# 1W_FM_TRX_DRA818V.net
KiCad netlist of a schematic drawn in EAGLE
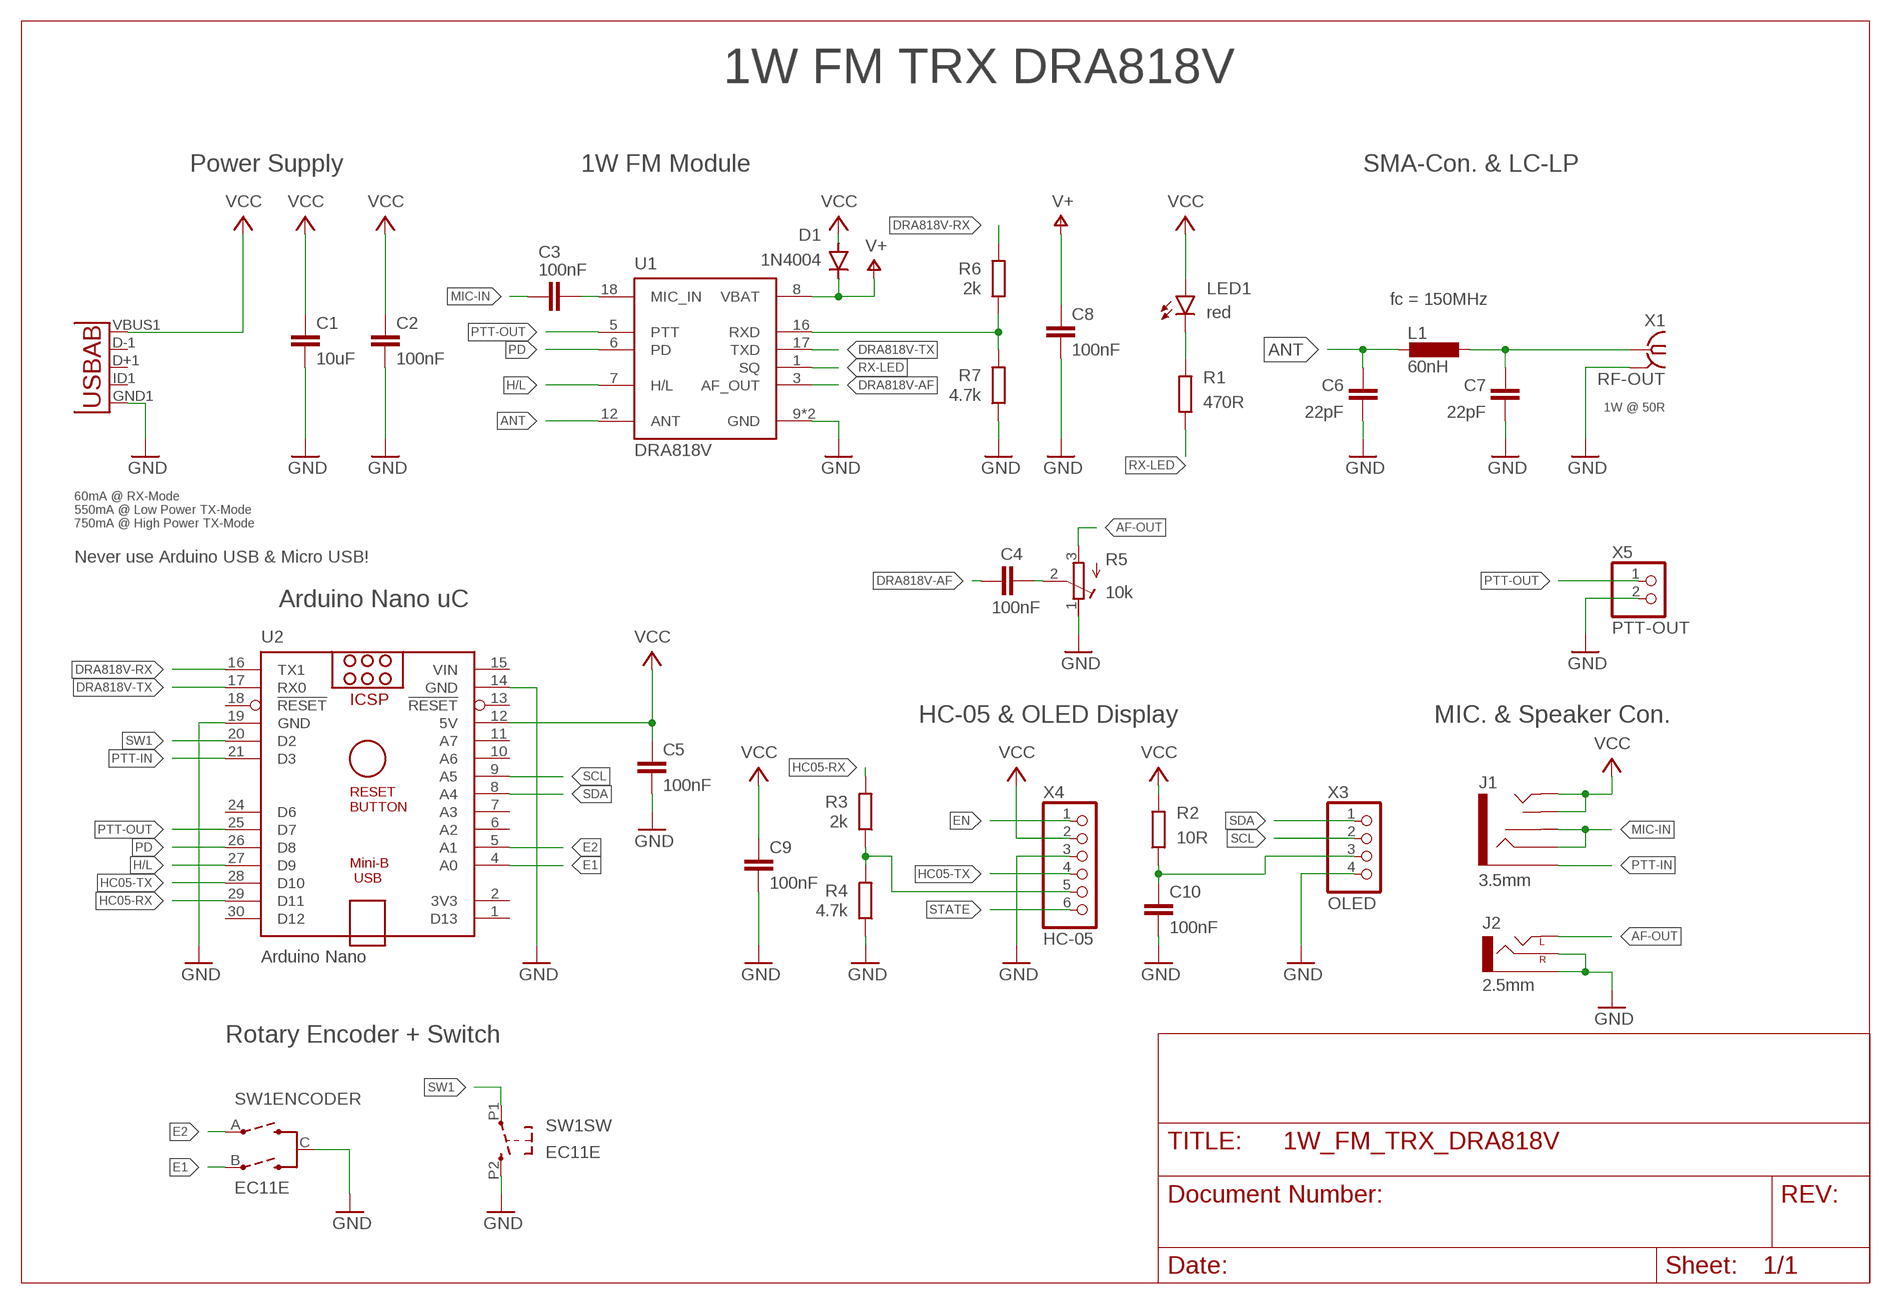
[diagram p0: schematic, sheet 1]

(export (version "E")
  (design (tool "Eeschema 10.0.6"))
  (components
    (comp (ref "C1")
      (value "10uF")
      (footprint "eagle-import:C0805K")
      (libsource (lib "eagle-import") (part "C-EUC0805K"))
    )
    (comp (ref "C2")
      (value "100nF")
      (footprint "eagle-import:C0805K")
      (libsource (lib "eagle-import") (part "C-EUC0805K"))
    )
    (comp (ref "C3")
      (value "100nF")
      (footprint "eagle-import:C0805K")
      (libsource (lib "eagle-import") (part "C-EUC0805K"))
    )
    (comp (ref "C4")
      (value "100nF")
      (footprint "eagle-import:C0805K")
      (libsource (lib "eagle-import") (part "C-EUC0805K"))
    )
    (comp (ref "C5")
      (value "100nF")
      (footprint "eagle-import:C0805K")
      (libsource (lib "eagle-import") (part "C-EUC0805K"))
    )
    (comp (ref "C6")
      (value "22pF")
      (footprint "eagle-import:C0805K")
      (libsource (lib "eagle-import") (part "C-EUC0805K"))
    )
    (comp (ref "C7")
      (value "22pF")
      (footprint "eagle-import:C0805K")
      (libsource (lib "eagle-import") (part "C-EUC0805K"))
    )
    (comp (ref "C8")
      (value "100nF")
      (footprint "eagle-import:C0805K")
      (libsource (lib "eagle-import") (part "C-EUC0805K"))
    )
    (comp (ref "C9")
      (value "100nF")
      (footprint "eagle-import:C0805K")
      (libsource (lib "eagle-import") (part "C-EUC0805K"))
    )
    (comp (ref "C10")
      (value "100nF")
      (footprint "eagle-import:C0805K")
      (libsource (lib "eagle-import") (part "C-EUC0805K"))
    )
    (comp (ref "D1")
      (value "1N4004")
      (footprint "eagle-import:DO41-10")
      (libsource (lib "eagle-import") (part "1N4004"))
    )
    (comp (ref "J1")
      (value "3.5mm")
      (footprint "eagle-import:AUDIO-JACK")
      (libsource (lib "eagle-import") (part "AUDIO_JACK_3.5MM_PTH"))
    )
    (comp (ref "J2")
      (value "2.5mm")
      (footprint "eagle-import:STEREOJACK2.5MM_STEREOJACK2.5MM")
      (libsource (lib "eagle-import") (part "AUDIO_JACK_2.5MM_2.5MM"))
    )
    (comp (ref "L1")
      (value "60nH")
      (footprint "eagle-import:L8530M")
      (libsource (lib "eagle-import") (part "L-EUL8530M"))
    )
    (comp (ref "LED1")
      (value "red")
      (footprint "eagle-import:CHIP-LED0805")
      (libsource (lib "eagle-import") (part "LEDCHIP-LED0805"))
    )
    (comp (ref "R1")
      (value "470R")
      (footprint "eagle-import:R0805")
      (libsource (lib "eagle-import") (part "R-EU_R0805"))
    )
    (comp (ref "R2")
      (value "10R")
      (footprint "eagle-import:R0805")
      (libsource (lib "eagle-import") (part "R-EU_R0805"))
    )
    (comp (ref "R3")
      (value "2k")
      (footprint "eagle-import:R0805")
      (libsource (lib "eagle-import") (part "R-EU_R0805"))
    )
    (comp (ref "R4")
      (value "4.7k")
      (footprint "eagle-import:R0805")
      (libsource (lib "eagle-import") (part "R-EU_R0805"))
    )
    (comp (ref "R5")
      (value "10k")
      (footprint "eagle-import:RTRIM3314J")
      (libsource (lib "eagle-import") (part "R-TRIMM3314J"))
    )
    (comp (ref "R6")
      (value "2k")
      (footprint "eagle-import:R0805")
      (libsource (lib "eagle-import") (part "R-EU_R0805"))
    )
    (comp (ref "R7")
      (value "4.7k")
      (footprint "eagle-import:R0805")
      (libsource (lib "eagle-import") (part "R-EU_R0805"))
    )
    (comp (ref "SW1")
      (value "EC11E")
      (footprint "eagle-import:EC11E_INCREMENTAL_ENCODER")
      (libsource (lib "eagle-import") (part "ENCODER_SW1-PEC12"))
    )
    (comp (ref "U1")
      (value "DRA818V")
      (footprint "eagle-import:DORJI_DRA818V")
      (fields (field (name "MF") "DORJI"))
      (libsource (lib "eagle-import") (part "DRA818V"))
    )
    (comp (ref "U2")
      (value "Arduino Nano")
      (footprint "eagle-import:ARDUINO_NANO")
      (libsource (lib "eagle-import") (part "ARDUINO_NANO"))
    )
    (comp (ref "U3")
      (value "USB Micro")
      (footprint "eagle-import:USB-MICRO-SMD")
      (libsource (lib "eagle-import") (part "USB{dblquote}{dblquote}"))
    )
    (comp (ref "X1")
      (value "RF-OUT")
      (footprint "eagle-import:J502-ND-142-0711-821_826")
      (fields (field (name "MF") "JOHNSON COMPONENTS") (field (name "MPN") "142-0711-821"))
      (libsource (lib "eagle-import") (part "SMA-PCB-CON142-0711-821/826"))
    )
    (comp (ref "X3")
      (value "OLED")
      (footprint "eagle-import:1X04")
      (libsource (lib "eagle-import") (part "PINHD-1X4"))
    )
    (comp (ref "X4")
      (value "HC-05")
      (footprint "eagle-import:1X06")
      (libsource (lib "eagle-import") (part "PINHD-1X6"))
    )
    (comp (ref "X5")
      (value "PTT-OUT")
      (footprint "eagle-import:1X02")
      (libsource (lib "eagle-import") (part "PINHD-1X2"))
    )
  )
  (nets
    (net (code "1") (name "/VIN") (class "Default")
      (node (ref "U2") (pin "15") (pinfunction "VIN_15") (pintype "power_in"))
    )
    (net (code "2") (name "AF-OUT") (class "Default")
      (node (ref "J2") (pin "SHIELD") (pinfunction "LEFT_SHIELD") (pintype "bidirectional"))
      (node (ref "R5") (pin "3") (pinfunction "A_3") (pintype "passive"))
    )
    (net (code "3") (name "ANT") (class "Default")
      (node (ref "C6") (pin "2") (pinfunction "2_2") (pintype "passive"))
      (node (ref "L1") (pin "2") (pinfunction "2_2") (pintype "passive"))
      (node (ref "U1") (pin "12") (pinfunction "ANT_12") (pintype "passive"))
    )
    (net (code "4") (name "DRA818V-AF") (class "Default")
      (node (ref "C4") (pin "1") (pinfunction "1_1") (pintype "passive"))
      (node (ref "U1") (pin "3") (pinfunction "AF_OUT_3") (pintype "output"))
    )
    (net (code "5") (name "DRA818V-RX") (class "Default")
      (node (ref "R6") (pin "2") (pinfunction "2_2") (pintype "passive"))
      (node (ref "U2") (pin "16") (pinfunction "TX1_16") (pintype "bidirectional"))
    )
    (net (code "6") (name "DRA818V-TX") (class "Default")
      (node (ref "U1") (pin "17") (pinfunction "TXD_17") (pintype "output"))
      (node (ref "U2") (pin "17") (pinfunction "RX0_17") (pintype "bidirectional"))
    )
    (net (code "7") (name "E1") (class "Default")
      (node (ref "SW1") (pin "B") (pinfunction "B_B") (pintype "passive"))
      (node (ref "U2") (pin "4") (pinfunction "A0_4") (pintype "bidirectional"))
    )
    (net (code "8") (name "E2") (class "Default")
      (node (ref "SW1") (pin "A") (pinfunction "A_A") (pintype "passive"))
      (node (ref "U2") (pin "5") (pinfunction "A1_5") (pintype "bidirectional"))
    )
    (net (code "9") (name "EN") (class "Default")
      (node (ref "X4") (pin "1") (pinfunction "1_1") (pintype "passive"))
    )
    (net (code "10") (name "GND") (class "Default")
      (node (ref "C1") (pin "2") (pinfunction "2_2") (pintype "passive"))
      (node (ref "C10") (pin "2") (pinfunction "2_2") (pintype "passive"))
      (node (ref "C2") (pin "2") (pinfunction "2_2") (pintype "passive"))
      (node (ref "C5") (pin "2") (pinfunction "2_2") (pintype "passive"))
      (node (ref "C6") (pin "1") (pinfunction "1_1") (pintype "passive"))
      (node (ref "C7") (pin "1") (pinfunction "1_1") (pintype "passive"))
      (node (ref "C8") (pin "1") (pinfunction "1_1") (pintype "passive"))
      (node (ref "C9") (pin "2") (pinfunction "2_2") (pintype "passive"))
      (node (ref "J2") (pin "RING1") (pinfunction "SLEEVE_RING1") (pintype "bidirectional"))
      (node (ref "J2") (pin "TIP") (pinfunction "RIGHT_TIP") (pintype "bidirectional"))
      (node (ref "R4") (pin "1") (pinfunction "1_1") (pintype "passive"))
      (node (ref "R5") (pin "1") (pinfunction "E_1") (pintype "passive"))
      (node (ref "R7") (pin "1") (pinfunction "1_1") (pintype "passive"))
      (node (ref "SW1") (pin "C") (pinfunction "C_C") (pintype "passive"))
      (node (ref "SW1") (pin "P2") (pinfunction "2_P2") (pintype "passive"))
      (node (ref "U1") (pin "10") (pinfunction "GND_10") (pintype "power_in"))
      (node (ref "U1") (pin "9") (pinfunction "GND_9") (pintype "power_in"))
      (node (ref "U2") (pin "14") (pinfunction "GND_14") (pintype "power_in"))
      (node (ref "U2") (pin "19") (pinfunction "GND_19") (pintype "power_in"))
      (node (ref "U3") (pin "GND1") (pinfunction "GND_GND1") (pintype "bidirectional"))
      (node (ref "X1") (pin "G@1") (pinfunction "GND_G@1") (pintype "passive"))
      (node (ref "X1") (pin "G@2") (pinfunction "GND_G@2") (pintype "passive"))
      (node (ref "X1") (pin "G@3") (pinfunction "GND_G@3") (pintype "passive"))
      (node (ref "X1") (pin "G@4") (pinfunction "GND_G@4") (pintype "passive"))
      (node (ref "X3") (pin "4") (pinfunction "4_4") (pintype "passive"))
      (node (ref "X4") (pin "3") (pinfunction "3_3") (pintype "passive"))
      (node (ref "X5") (pin "2") (pinfunction "2_2") (pintype "passive"))
    )
    (net (code "11") (name "HC05-RX") (class "Default")
      (node (ref "R3") (pin "2") (pinfunction "2_2") (pintype "passive"))
      (node (ref "U2") (pin "29") (pinfunction "D11_29") (pintype "bidirectional"))
    )
    (net (code "12") (name "HC05-TX") (class "Default")
      (node (ref "U2") (pin "28") (pinfunction "D10_28") (pintype "bidirectional"))
      (node (ref "X4") (pin "4") (pinfunction "4_4") (pintype "passive"))
    )
    (net (code "13") (name "H{slash}L") (class "Default")
      (node (ref "U1") (pin "7") (pinfunction "H/L_7") (pintype "input"))
      (node (ref "U2") (pin "27") (pinfunction "D9_27") (pintype "bidirectional"))
    )
    (net (code "14") (name "MIC-IN") (class "Default")
      (node (ref "C3") (pin "1") (pinfunction "1_1") (pintype "passive"))
      (node (ref "J1") (pin "RING") (pinfunction "RING_RING") (pintype "bidirectional"))
      (node (ref "J1") (pin "RSH") (pinfunction "RSH_RSH") (pintype "bidirectional"))
    )
    (net (code "15") (name "Net-(C10-Pad1)") (class "Default")
      (node (ref "C10") (pin "1") (pinfunction "1_1") (pintype "passive"))
      (node (ref "R2") (pin "1") (pinfunction "1_1") (pintype "passive"))
      (node (ref "X3") (pin "3") (pinfunction "3_3") (pintype "passive"))
    )
    (net (code "16") (name "Net-(LED1-PadC)") (class "Default")
      (node (ref "LED1") (pin "C") (pinfunction "C_C") (pintype "passive"))
      (node (ref "R1") (pin "2") (pinfunction "2_2") (pintype "passive"))
    )
    (net (code "17") (name "Net-(R3-Pad1)") (class "Default")
      (node (ref "R3") (pin "1") (pinfunction "1_1") (pintype "passive"))
      (node (ref "R4") (pin "2") (pinfunction "2_2") (pintype "passive"))
      (node (ref "X4") (pin "5") (pinfunction "5_5") (pintype "passive"))
    )
    (net (code "18") (name "Net-(R5-S)") (class "Default")
      (node (ref "C4") (pin "2") (pinfunction "2_2") (pintype "passive"))
      (node (ref "R5") (pin "2") (pinfunction "S_2") (pintype "passive"))
    )
    (net (code "19") (name "Net-(U1-MIC_IN)") (class "Default")
      (node (ref "C3") (pin "2") (pinfunction "2_2") (pintype "passive"))
      (node (ref "U1") (pin "18") (pinfunction "MIC_IN_18") (pintype "input"))
    )
    (net (code "20") (name "Net-(U1-RXD)") (class "Default")
      (node (ref "R6") (pin "1") (pinfunction "1_1") (pintype "passive"))
      (node (ref "R7") (pin "2") (pinfunction "2_2") (pintype "passive"))
      (node (ref "U1") (pin "16") (pinfunction "RXD_16") (pintype "input"))
    )
    (net (code "21") (name "Net-(X1-RF)") (class "Default")
      (node (ref "C7") (pin "2") (pinfunction "2_2") (pintype "passive"))
      (node (ref "L1") (pin "1") (pinfunction "1_1") (pintype "passive"))
      (node (ref "X1") (pin "1") (pinfunction "RF_1") (pintype "passive"))
    )
    (net (code "22") (name "PD") (class "Default")
      (node (ref "U1") (pin "6") (pinfunction "PD_6") (pintype "input"))
      (node (ref "U2") (pin "26") (pinfunction "D8_26") (pintype "bidirectional"))
    )
    (net (code "23") (name "PTT-IN") (class "Default")
      (node (ref "J1") (pin "SLEEVE") (pinfunction "SLEEVE_SLEEVE") (pintype "bidirectional"))
      (node (ref "U2") (pin "21") (pinfunction "D3_21") (pintype "bidirectional"))
    )
    (net (code "24") (name "PTT-OUT") (class "Default")
      (node (ref "U1") (pin "5") (pinfunction "PTT_5") (pintype "input"))
      (node (ref "U2") (pin "25") (pinfunction "D7_25") (pintype "bidirectional"))
      (node (ref "X5") (pin "1") (pinfunction "1_1") (pintype "passive"))
    )
    (net (code "25") (name "RX-LED") (class "Default")
      (node (ref "R1") (pin "1") (pinfunction "1_1") (pintype "passive"))
      (node (ref "U1") (pin "1") (pinfunction "SQ_1") (pintype "output"))
    )
    (net (code "26") (name "SCL") (class "Default")
      (node (ref "U2") (pin "9") (pinfunction "A5_9") (pintype "bidirectional"))
      (node (ref "X3") (pin "2") (pinfunction "2_2") (pintype "passive"))
    )
    (net (code "27") (name "SDA") (class "Default")
      (node (ref "U2") (pin "8") (pinfunction "A4_8") (pintype "bidirectional"))
      (node (ref "X3") (pin "1") (pinfunction "1_1") (pintype "passive"))
    )
    (net (code "28") (name "STATE") (class "Default")
      (node (ref "X4") (pin "6") (pinfunction "6_6") (pintype "passive"))
    )
    (net (code "29") (name "SW1") (class "Default")
      (node (ref "SW1") (pin "P1") (pinfunction "1_P1") (pintype "passive"))
      (node (ref "U2") (pin "20") (pinfunction "D2_20") (pintype "bidirectional"))
    )
    (net (code "30") (name "V+") (class "Default")
      (node (ref "C8") (pin "2") (pinfunction "2_2") (pintype "passive"))
      (node (ref "D1") (pin "C") (pinfunction "C_C") (pintype "passive"))
      (node (ref "U1") (pin "8") (pinfunction "VBAT_8") (pintype "power_in"))
    )
    (net (code "31") (name "VCC") (class "Default")
      (node (ref "C1") (pin "1") (pinfunction "1_1") (pintype "passive"))
      (node (ref "C2") (pin "1") (pinfunction "1_1") (pintype "passive"))
      (node (ref "C5") (pin "1") (pinfunction "1_1") (pintype "passive"))
      (node (ref "C9") (pin "1") (pinfunction "1_1") (pintype "passive"))
      (node (ref "D1") (pin "A") (pinfunction "A_A") (pintype "passive"))
      (node (ref "J1") (pin "TIP") (pinfunction "TIP_TIP") (pintype "bidirectional"))
      (node (ref "J1") (pin "TSH") (pinfunction "TSH_TSH") (pintype "bidirectional"))
      (node (ref "LED1") (pin "A") (pinfunction "A_A") (pintype "passive"))
      (node (ref "R2") (pin "2") (pinfunction "2_2") (pintype "passive"))
      (node (ref "U2") (pin "12") (pinfunction "5V_12") (pintype "power_in"))
      (node (ref "U3") (pin "VBUS1") (pinfunction "VBUS_VBUS1") (pintype "bidirectional"))
      (node (ref "X4") (pin "2") (pinfunction "2_2") (pintype "passive"))
    )
    (net (code "32") (name "unconnected-(U2-3V3-Pad2)") (class "Default")
      (node (ref "U2") (pin "2") (pinfunction "3V3_2") (pintype "output"))
    )
    (net (code "33") (name "unconnected-(U2-A2-Pad6)") (class "Default")
      (node (ref "U2") (pin "6") (pinfunction "A2_6") (pintype "bidirectional"))
    )
    (net (code "34") (name "unconnected-(U2-A3-Pad7)") (class "Default")
      (node (ref "U2") (pin "7") (pinfunction "A3_7") (pintype "bidirectional"))
    )
    (net (code "35") (name "unconnected-(U2-A6-Pad10)") (class "Default")
      (node (ref "U2") (pin "10") (pinfunction "A6_10") (pintype "bidirectional"))
    )
    (net (code "36") (name "unconnected-(U2-A7-Pad11)") (class "Default")
      (node (ref "U2") (pin "11") (pinfunction "A7_11") (pintype "bidirectional"))
    )
    (net (code "37") (name "unconnected-(U2-D6-Pad24)") (class "Default")
      (node (ref "U2") (pin "24") (pinfunction "D6_24") (pintype "bidirectional"))
    )
    (net (code "38") (name "unconnected-(U2-D12-Pad30)") (class "Default")
      (node (ref "U2") (pin "30") (pinfunction "D12_30") (pintype "bidirectional"))
    )
    (net (code "39") (name "unconnected-(U2-D13-Pad1)") (class "Default")
      (node (ref "U2") (pin "1") (pinfunction "D13_1") (pintype "bidirectional"))
    )
    (net (code "40") (name "unconnected-(U2-~{RESET}-Pad13)") (class "Default")
      (node (ref "U2") (pin "13") (pinfunction "~{RESET}_13") (pintype "input"))
    )
    (net (code "41") (name "unconnected-(U2-~{RESET}-Pad18)") (class "Default")
      (node (ref "U2") (pin "18") (pinfunction "~{RESET}_18") (pintype "input"))
    )
    (net (code "42") (name "unconnected-(U3-D+-PadD+1)") (class "Default")
      (node (ref "U3") (pin "D+1") (pinfunction "D+_D+1") (pintype "bidirectional"))
    )
    (net (code "43") (name "unconnected-(U3-D--PadD-1)") (class "Default")
      (node (ref "U3") (pin "D-1") (pinfunction "D-_D-1") (pintype "bidirectional"))
    )
    (net (code "44") (name "unconnected-(U3-USBID-PadID1)") (class "Default")
      (node (ref "U3") (pin "ID1") (pinfunction "USBID_ID1") (pintype "bidirectional"))
    )
  )
)
